# rotor.net
KiCad netlist of a schematic drawn in EAGLE
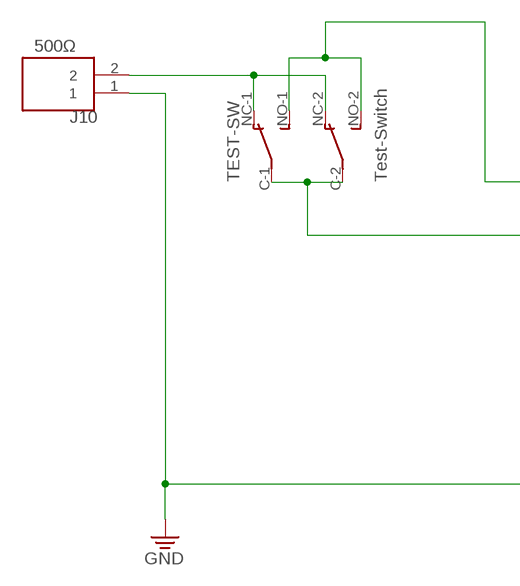
[diagram p0: schematic, sheet 1, part 1 of 2]
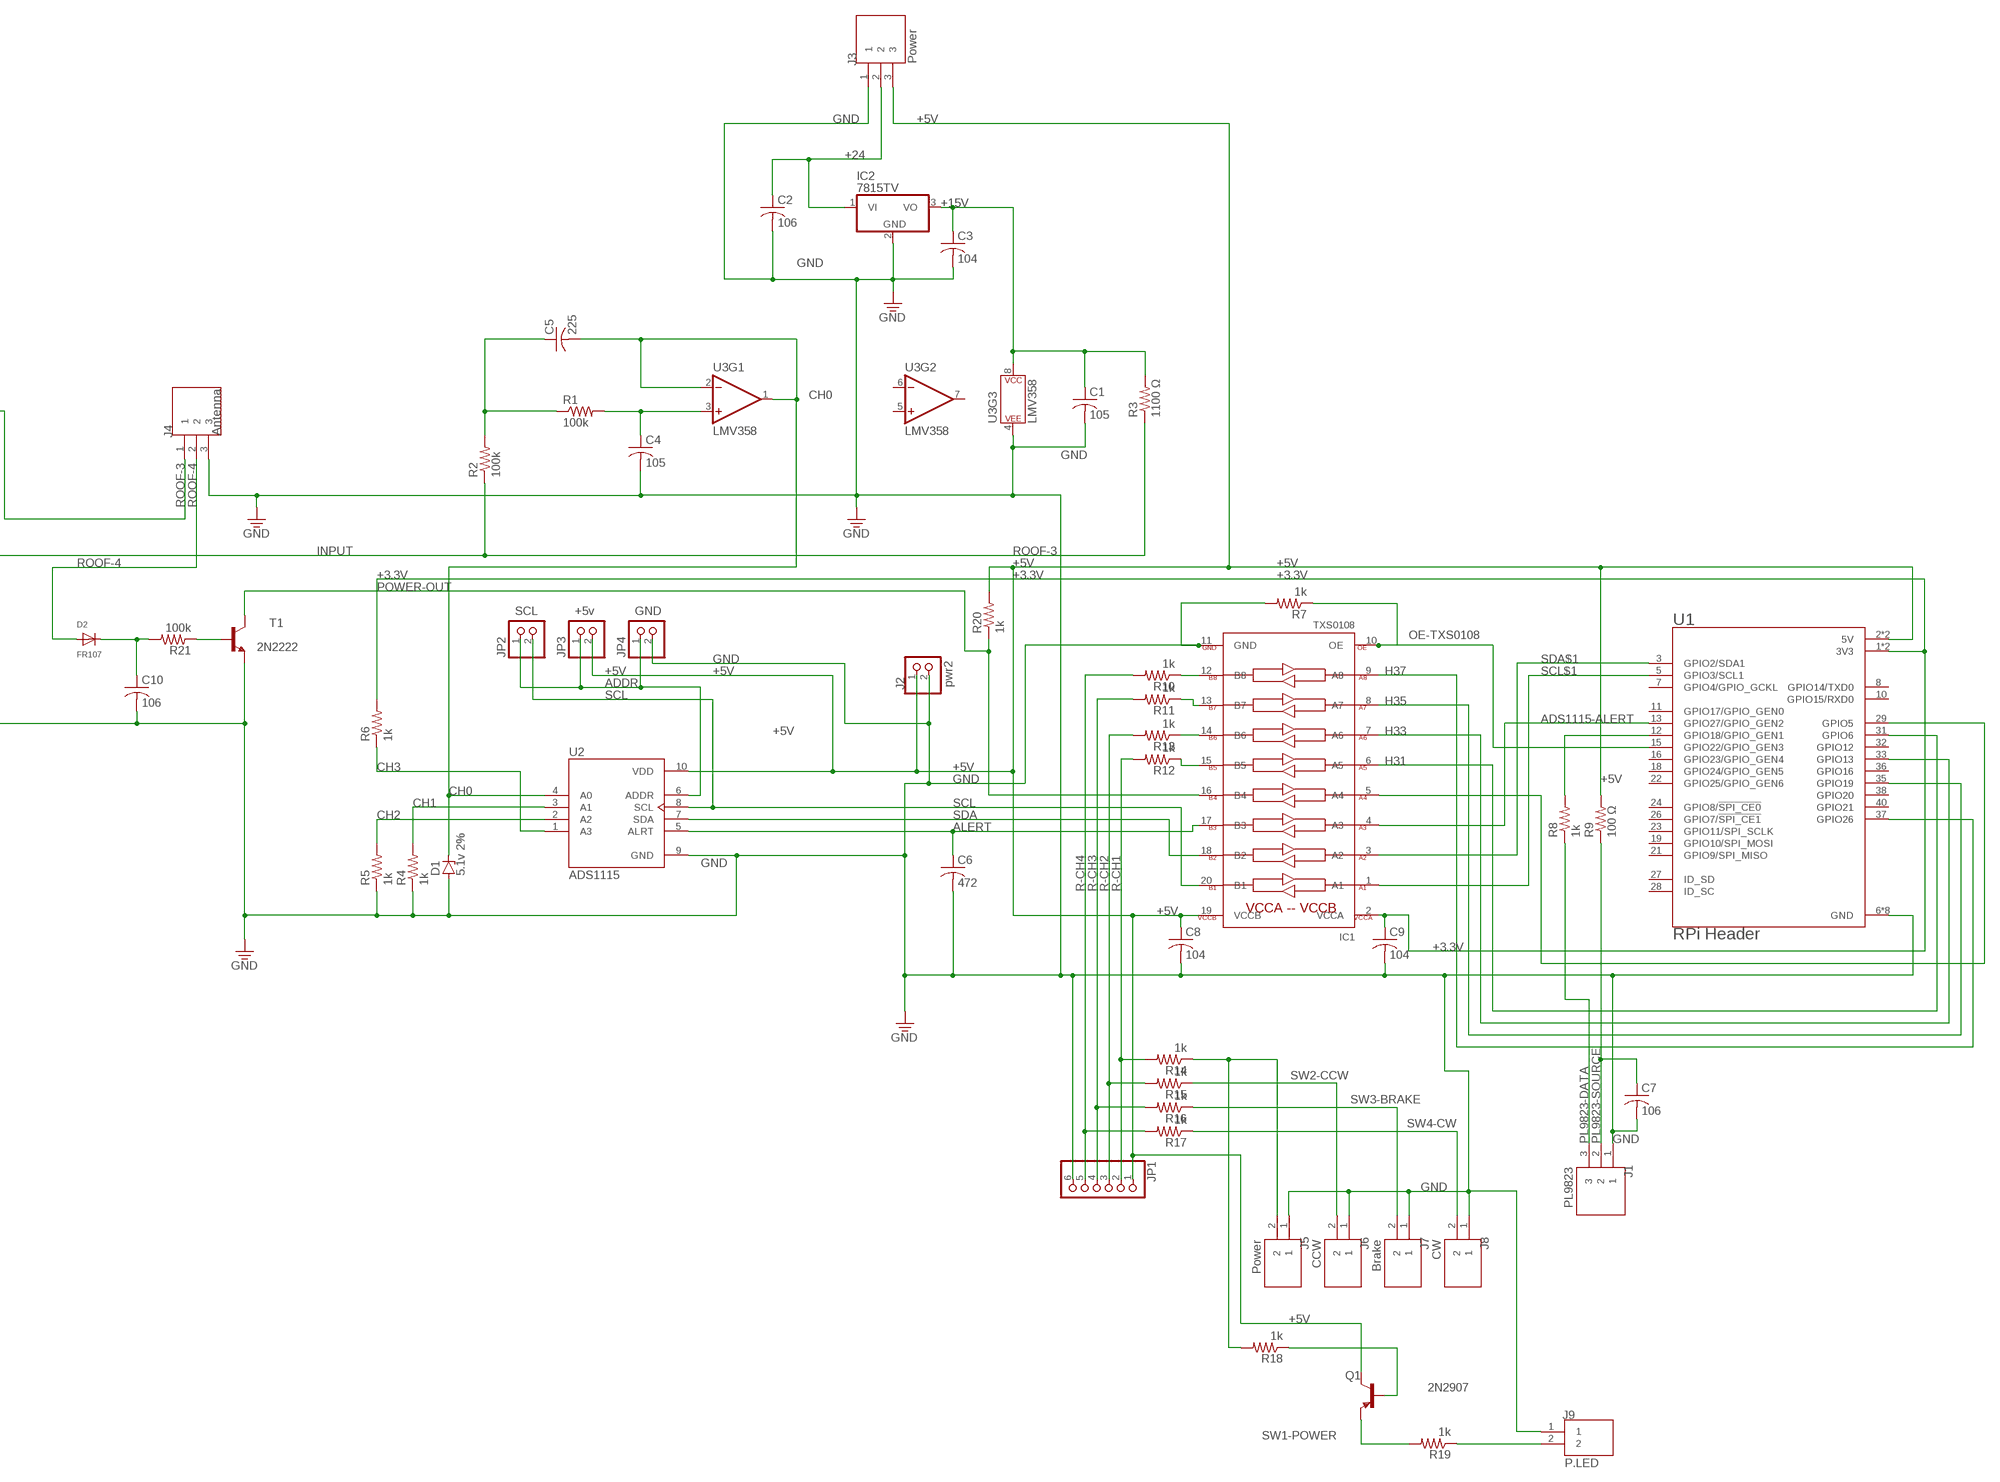
[diagram p1: schematic, sheet 1, part 2 of 2]

(export (version "E")
  (design (tool "Eeschema 10.0.6"))
  (components
    (comp (ref "C1")
      (value "105")
      (footprint "eagle-import:C0805")
      (libsource (lib "eagle-import") (part "C-USC0805"))
    )
    (comp (ref "C2")
      (value "106")
      (footprint "eagle-import:C0805")
      (libsource (lib "eagle-import") (part "C-USC0805"))
    )
    (comp (ref "C3")
      (value "104")
      (footprint "eagle-import:C0805")
      (libsource (lib "eagle-import") (part "C-USC0805"))
    )
    (comp (ref "C4")
      (value "105")
      (footprint "eagle-import:C0805")
      (libsource (lib "eagle-import") (part "C-USC0805"))
    )
    (comp (ref "C5")
      (value "225")
      (footprint "eagle-import:C0805")
      (libsource (lib "eagle-import") (part "C-USC0805"))
    )
    (comp (ref "C6")
      (value "472")
      (footprint "eagle-import:C0805")
      (libsource (lib "eagle-import") (part "C-USC0805"))
    )
    (comp (ref "C7")
      (value "106")
      (footprint "eagle-import:C0805")
      (libsource (lib "eagle-import") (part "C-USC0805"))
    )
    (comp (ref "C8")
      (value "104")
      (footprint "eagle-import:C0805")
      (libsource (lib "eagle-import") (part "C-USC0805"))
    )
    (comp (ref "C9")
      (value "104")
      (footprint "eagle-import:C0805")
      (libsource (lib "eagle-import") (part "C-USC0805"))
    )
    (comp (ref "C10")
      (value "106")
      (footprint "eagle-import:C0805")
      (libsource (lib "eagle-import") (part "C-USC0805"))
    )
    (comp (ref "D1")
      (value "5.1v 2%")
      (footprint "eagle-import:ZDIO-7.5")
      (libsource (lib "eagle-import") (part "ZENER-DIODEZD-7.5"))
    )
    (comp (ref "D2")
      (value "FR107")
      (footprint "eagle-import:SMADIODE")
      (libsource (lib "eagle-import") (part "DIODESMA"))
    )
    (comp (ref "IC1")
      (value "TXS0108")
      (footprint "eagle-import:TSSOP20")
      (fields (field (name "MF") "Texas Instruments") (field (name "MP") "TXS0108E"))
      (libsource (lib "eagle-import") (part "TXS0108EPWR"))
    )
    (comp (ref "IC2")
      (value "7815TV")
      (footprint "eagle-import:TO220V")
      (libsource (lib "eagle-import") (part "78TV15"))
    )
    (comp (ref "J1")
      (value "PL9823")
      (footprint "eagle-import:CUI_TB004-508-03BE")
      (fields (field (name "MF") "CUI Devices") (field (name "MP") "TB004 -508-03BE"))
      (libsource (lib "eagle-import") (part "TB004-508-03BE"))
    )
    (comp (ref "J2")
      (value "pwr2")
      (footprint "eagle-import:1X02")
      (libsource (lib "eagle-import") (part "pinhead_325_PINHD-1X2"))
    )
    (comp (ref "J3")
      (value "Power")
      (footprint "eagle-import:CUI_TB004-508-03BE")
      (fields (field (name "MF") "CUI Devices") (field (name "MP") "TB004 -508-03BE"))
      (libsource (lib "eagle-import") (part "TB004-508-03BE"))
    )
    (comp (ref "J4")
      (value "Antenna")
      (footprint "eagle-import:CUI_TB004-508-03BE")
      (fields (field (name "MF") "CUI Devices") (field (name "MP") "TB004 -508-03BE"))
      (libsource (lib "eagle-import") (part "TB004-508-03BE"))
    )
    (comp (ref "J5")
      (value "Power")
      (footprint "eagle-import:CUI_TB004-508-02BE")
      (fields (field (name "MF") "CUI Devices") (field (name "MP") "TB004-508-02BE"))
      (libsource (lib "eagle-import") (part "TB004-508-02BE"))
    )
    (comp (ref "J6")
      (value "CCW")
      (footprint "eagle-import:CUI_TB004-508-02BE")
      (fields (field (name "MF") "CUI Devices") (field (name "MP") "TB004-508-02BE"))
      (libsource (lib "eagle-import") (part "TB004-508-02BE"))
    )
    (comp (ref "J7")
      (value "Brake")
      (footprint "eagle-import:CUI_TB004-508-02BE")
      (fields (field (name "MF") "CUI Devices") (field (name "MP") "TB004-508-02BE"))
      (libsource (lib "eagle-import") (part "TB004-508-02BE"))
    )
    (comp (ref "J8")
      (value "CW")
      (footprint "eagle-import:CUI_TB004-508-02BE")
      (fields (field (name "MF") "CUI Devices") (field (name "MP") "TB004-508-02BE"))
      (libsource (lib "eagle-import") (part "TB004-508-02BE"))
    )
    (comp (ref "J9")
      (value "P.LED")
      (footprint "eagle-import:CUI_TB004-508-02BE")
      (fields (field (name "MF") "CUI Devices") (field (name "MP") "TB004-508-02BE"))
      (libsource (lib "eagle-import") (part "TB004-508-02BE"))
    )
    (comp (ref "J10")
      (value "500Ω ├")
      (footprint "eagle-import:CUI_TB004-508-02BE")
      (fields (field (name "MF") "CUI Devices") (field (name "MP") "TB004-508-02BE"))
      (libsource (lib "eagle-import") (part "TB004-508-02BE"))
    )
    (comp (ref "JP1")
      (value "PINHD-1X6")
      (footprint "eagle-import:1X06")
      (libsource (lib "eagle-import") (part "PINHD-1X6"))
    )
    (comp (ref "JP2")
      (value "SCL")
      (footprint "eagle-import:1X02-SPECIAL")
      (libsource (lib "eagle-import") (part "PINHD-1X2SPECIAL"))
    )
    (comp (ref "JP3")
      (value "+5v")
      (footprint "eagle-import:1X02-SPECIAL")
      (libsource (lib "eagle-import") (part "PINHD-1X2SPECIAL"))
    )
    (comp (ref "JP4")
      (value "GND")
      (footprint "eagle-import:1X02-SPECIAL")
      (libsource (lib "eagle-import") (part "PINHD-1X2SPECIAL"))
    )
    (comp (ref "Q1")
      (value "2N2907")
      (footprint "eagle-import:TO92-CBE-OVAL")
      (libsource (lib "eagle-import") (part "2N2907CBE"))
    )
    (comp (ref "R1")
      (value "100k")
      (footprint "eagle-import:M0805")
      (libsource (lib "eagle-import") (part "test_R-US_M0805"))
    )
    (comp (ref "R2")
      (value "100k")
      (footprint "eagle-import:M0805")
      (libsource (lib "eagle-import") (part "test_R-US_M0805"))
    )
    (comp (ref "R3")
      (value "1100 Ω")
      (footprint "eagle-import:M0805")
      (libsource (lib "eagle-import") (part "R-US_M0805"))
    )
    (comp (ref "R4")
      (value "1k")
      (footprint "eagle-import:M0805")
      (libsource (lib "eagle-import") (part "test_R-US_M0805"))
    )
    (comp (ref "R5")
      (value "1k")
      (footprint "eagle-import:M0805")
      (libsource (lib "eagle-import") (part "test_R-US_M0805"))
    )
    (comp (ref "R6")
      (value "1k")
      (footprint "eagle-import:M0805")
      (libsource (lib "eagle-import") (part "test_R-US_M0805"))
    )
    (comp (ref "R7")
      (value "1k")
      (footprint "eagle-import:M0805")
      (libsource (lib "eagle-import") (part "test_R-US_M0805"))
    )
    (comp (ref "R8")
      (value "1k")
      (footprint "eagle-import:M0805")
      (libsource (lib "eagle-import") (part "test_R-US_M0805"))
    )
    (comp (ref "R9")
      (value "100 Ω")
      (footprint "eagle-import:M0805")
      (libsource (lib "eagle-import") (part "test_R-US_M0805"))
    )
    (comp (ref "R10")
      (value "1k")
      (footprint "eagle-import:M0805")
      (libsource (lib "eagle-import") (part "test_R-US_M0805"))
    )
    (comp (ref "R11")
      (value "1k")
      (footprint "eagle-import:M0805")
      (libsource (lib "eagle-import") (part "test_R-US_M0805"))
    )
    (comp (ref "R12")
      (value "1k")
      (footprint "eagle-import:M0805")
      (libsource (lib "eagle-import") (part "test_R-US_M0805"))
    )
    (comp (ref "R13")
      (value "1k")
      (footprint "eagle-import:M0805")
      (libsource (lib "eagle-import") (part "test_R-US_M0805"))
    )
    (comp (ref "R14")
      (value "1k")
      (footprint "eagle-import:M0805")
      (libsource (lib "eagle-import") (part "test_R-US_M0805"))
    )
    (comp (ref "R15")
      (value "1k")
      (footprint "eagle-import:M0805")
      (libsource (lib "eagle-import") (part "test_R-US_M0805"))
    )
    (comp (ref "R16")
      (value "1k")
      (footprint "eagle-import:M0805")
      (libsource (lib "eagle-import") (part "test_R-US_M0805"))
    )
    (comp (ref "R17")
      (value "1k")
      (footprint "eagle-import:M0805")
      (libsource (lib "eagle-import") (part "test_R-US_M0805"))
    )
    (comp (ref "R18")
      (value "1k")
      (footprint "eagle-import:M0805")
      (libsource (lib "eagle-import") (part "test_R-US_M0805"))
    )
    (comp (ref "R19")
      (value "1k")
      (footprint "eagle-import:M0805")
      (libsource (lib "eagle-import") (part "test_R-US_M0805"))
    )
    (comp (ref "R20")
      (value "1k")
      (footprint "eagle-import:M0805")
      (libsource (lib "eagle-import") (part "test_R-US_M0805"))
    )
    (comp (ref "R21")
      (value "100k")
      (footprint "eagle-import:M0805")
      (libsource (lib "eagle-import") (part "test_R-US_M0805"))
    )
    (comp (ref "T1")
      (value "2N2222")
      (footprint "eagle-import:TO92-CBE-OVAL")
      (libsource (lib "eagle-import") (part "2N2222CBE"))
    )
    (comp (ref "TEST-SW")
      (value "Test-Switch")
      (footprint "eagle-import:DP-DT")
      (libsource (lib "eagle-import") (part "DPDT-SWITCH"))
    )
    (comp (ref "U1")
      (value "RPi Header")
      (footprint "eagle-import:MODULE_RASPBERRY_PI_3B+_HDR")
      (libsource (lib "eagle-import") (part "RASPBERRY_PI_3B+_HDRMODEL_RASPBEERY_PI_3B_HDR"))
    )
    (comp (ref "U2")
      (value "ADS1115")
      (footprint "eagle-import:MODULE_1115_NARROW")
      (fields (field (name "MF") "Adafruit Industries") (field (name "MP") "1085"))
      (libsource (lib "eagle-import") (part "ADS1115-BREAKOUT-NARROW"))
    )
    (comp (ref "U3")
      (value "LMV358")
      (footprint "eagle-import:SO08")
      (libsource (lib "eagle-import") (part "LM358-SOP8SOIC"))
    )
  )
  (nets
    (net (code "1") (name "/+3.3V") (class "Default")
      (node (ref "C9") (pin "1") (pinfunction "1_1") (pintype "passive"))
      (node (ref "IC1") (pin "2") (pinfunction "VCCA_2") (pintype "power_in"))
      (node (ref "R6") (pin "2") (pinfunction "2_2") (pintype "passive"))
      (node (ref "U1") (pin "1") (pinfunction "3V3_1") (pintype "power_in"))
      (node (ref "U1") (pin "17") (pinfunction "3V3_17") (pintype "power_in"))
    )
    (net (code "2") (name "/+5V") (class "Default")
      (node (ref "C8") (pin "1") (pinfunction "1_1") (pintype "passive"))
      (node (ref "IC1") (pin "19") (pinfunction "VCCB_19") (pintype "power_in"))
      (node (ref "J2") (pin "1") (pinfunction "1_1") (pintype "passive"))
      (node (ref "J3") (pin "3") (pinfunction "3_3") (pintype "passive"))
      (node (ref "JP1") (pin "1") (pinfunction "1_1") (pintype "passive"))
      (node (ref "JP3") (pin "2") (pinfunction "2_2") (pintype "passive"))
      (node (ref "Q1") (pin "C") (pinfunction "C_C") (pintype "passive"))
      (node (ref "R20") (pin "2") (pinfunction "2_2") (pintype "passive"))
      (node (ref "R9") (pin "2") (pinfunction "2_2") (pintype "passive"))
      (node (ref "U1") (pin "2") (pinfunction "5V_2") (pintype "power_in"))
      (node (ref "U1") (pin "4") (pinfunction "5V_4") (pintype "power_in"))
      (node (ref "U2") (pin "10") (pinfunction "VDD_10") (pintype "power_in"))
    )
    (net (code "3") (name "/+15V") (class "Default")
      (node (ref "C1") (pin "1") (pinfunction "1_1") (pintype "passive"))
      (node (ref "C3") (pin "1") (pinfunction "1_1") (pintype "passive"))
      (node (ref "IC2") (pin "3") (pinfunction "VO_3") (pintype "passive"))
      (node (ref "R3") (pin "2") (pinfunction "2_2") (pintype "passive"))
      (node (ref "U3") (pin "8") (pinfunction "P$V+_8") (pintype "bidirectional"))
    )
    (net (code "4") (name "/+24") (class "Default")
      (node (ref "C2") (pin "1") (pinfunction "1_1") (pintype "passive"))
      (node (ref "IC2") (pin "1") (pinfunction "VI_1") (pintype "input"))
      (node (ref "J3") (pin "2") (pinfunction "2_2") (pintype "passive"))
    )
    (net (code "5") (name "/ADDR") (class "Default")
      (node (ref "JP2") (pin "1") (pinfunction "1_1") (pintype "passive"))
      (node (ref "JP3") (pin "1") (pinfunction "1_1") (pintype "passive"))
      (node (ref "JP4") (pin "1") (pinfunction "1_1") (pintype "passive"))
      (node (ref "U2") (pin "6") (pinfunction "ADDR_6") (pintype "input"))
    )
    (net (code "6") (name "/ADS1115-ALERT") (class "Default")
      (node (ref "IC1") (pin "4") (pinfunction "A3_4") (pintype "bidirectional"))
      (node (ref "U1") (pin "13") (pinfunction "GPIO27/GPIO_GEN2_13") (pintype "bidirectional"))
    )
    (net (code "7") (name "/ALERT") (class "Default")
      (node (ref "C6") (pin "1") (pinfunction "1_1") (pintype "passive"))
      (node (ref "IC1") (pin "17") (pinfunction "B3_17") (pintype "bidirectional"))
      (node (ref "U2") (pin "5") (pinfunction "ALRT_5") (pintype "output"))
    )
    (net (code "8") (name "/CH0") (class "Default")
      (node (ref "C5") (pin "2") (pinfunction "2_2") (pintype "passive"))
      (node (ref "D1") (pin "C") (pinfunction "C_C") (pintype "passive"))
      (node (ref "U2") (pin "4") (pinfunction "A0_4") (pintype "input"))
      (node (ref "U3") (pin "1") (pinfunction "OUT_1") (pintype "output"))
      (node (ref "U3") (pin "2") (pinfunction "-IN_2") (pintype "input"))
    )
    (net (code "9") (name "/CH1") (class "Default")
      (node (ref "R4") (pin "2") (pinfunction "2_2") (pintype "passive"))
      (node (ref "U2") (pin "3") (pinfunction "A1_3") (pintype "input"))
    )
    (net (code "10") (name "/CH2") (class "Default")
      (node (ref "R5") (pin "2") (pinfunction "2_2") (pintype "passive"))
      (node (ref "U2") (pin "2") (pinfunction "A2_2") (pintype "input"))
    )
    (net (code "11") (name "/CH3") (class "Default")
      (node (ref "R6") (pin "1") (pinfunction "1_1") (pintype "passive"))
      (node (ref "U2") (pin "1") (pinfunction "A3_1") (pintype "input"))
    )
    (net (code "12") (name "/H31") (class "Default")
      (node (ref "IC1") (pin "6") (pinfunction "A5_6") (pintype "bidirectional"))
      (node (ref "U1") (pin "31") (pinfunction "GPIO6_31") (pintype "bidirectional"))
    )
    (net (code "13") (name "/H33") (class "Default")
      (node (ref "IC1") (pin "7") (pinfunction "A6_7") (pintype "bidirectional"))
      (node (ref "U1") (pin "33") (pinfunction "GPIO13_33") (pintype "bidirectional"))
    )
    (net (code "14") (name "/H35") (class "Default")
      (node (ref "IC1") (pin "8") (pinfunction "A7_8") (pintype "bidirectional"))
      (node (ref "U1") (pin "35") (pinfunction "GPIO19_35") (pintype "bidirectional"))
    )
    (net (code "15") (name "/H37") (class "Default")
      (node (ref "IC1") (pin "9") (pinfunction "A8_9") (pintype "bidirectional"))
      (node (ref "U1") (pin "37") (pinfunction "GPIO26_37") (pintype "bidirectional"))
    )
    (net (code "16") (name "/INPUT") (class "Default")
      (node (ref "R2") (pin "1") (pinfunction "1_1") (pintype "passive"))
      (node (ref "R3") (pin "1") (pinfunction "1_1") (pintype "passive"))
      (node (ref "TEST-SW") (pin "C-1") (pinfunction "C-1_C-1") (pintype "passive"))
      (node (ref "TEST-SW") (pin "C-2") (pinfunction "C-2_C-2") (pintype "passive"))
    )
    (net (code "17") (name "/OE-TXS0108") (class "Default")
      (node (ref "IC1") (pin "10") (pinfunction "OE_10") (pintype "input"))
      (node (ref "R7") (pin "1") (pinfunction "1_1") (pintype "passive"))
      (node (ref "U1") (pin "15") (pinfunction "GPIO22/GPIO_GEN3_15") (pintype "bidirectional"))
    )
    (net (code "18") (name "/PL9823-DATA") (class "Default")
      (node (ref "J1") (pin "3") (pinfunction "3_3") (pintype "passive"))
      (node (ref "R8") (pin "1") (pinfunction "1_1") (pintype "passive"))
    )
    (net (code "19") (name "/PL9823-SOURCE") (class "Default")
      (node (ref "C7") (pin "1") (pinfunction "1_1") (pintype "passive"))
      (node (ref "J1") (pin "2") (pinfunction "2_2") (pintype "passive"))
      (node (ref "R9") (pin "1") (pinfunction "1_1") (pintype "passive"))
    )
    (net (code "20") (name "/POWER-OUT") (class "Default")
      (node (ref "IC1") (pin "16") (pinfunction "B4_16") (pintype "bidirectional"))
      (node (ref "R20") (pin "1") (pinfunction "1_1") (pintype "passive"))
      (node (ref "T1") (pin "C") (pinfunction "C_C") (pintype "passive"))
    )
    (net (code "21") (name "/R-CH1") (class "Default")
      (node (ref "JP1") (pin "2") (pinfunction "2_2") (pintype "passive"))
      (node (ref "R12") (pin "2") (pinfunction "2_2") (pintype "passive"))
      (node (ref "R14") (pin "2") (pinfunction "2_2") (pintype "passive"))
    )
    (net (code "22") (name "/R-CH2") (class "Default")
      (node (ref "JP1") (pin "3") (pinfunction "3_3") (pintype "passive"))
      (node (ref "R13") (pin "2") (pinfunction "2_2") (pintype "passive"))
      (node (ref "R15") (pin "2") (pinfunction "2_2") (pintype "passive"))
    )
    (net (code "23") (name "/R-CH3") (class "Default")
      (node (ref "JP1") (pin "4") (pinfunction "4_4") (pintype "passive"))
      (node (ref "R11") (pin "2") (pinfunction "2_2") (pintype "passive"))
      (node (ref "R16") (pin "2") (pinfunction "2_2") (pintype "passive"))
    )
    (net (code "24") (name "/R-CH4") (class "Default")
      (node (ref "JP1") (pin "5") (pinfunction "5_5") (pintype "passive"))
      (node (ref "R10") (pin "2") (pinfunction "2_2") (pintype "passive"))
      (node (ref "R17") (pin "2") (pinfunction "2_2") (pintype "passive"))
    )
    (net (code "25") (name "/ROOF-3") (class "Default")
      (node (ref "J4") (pin "1") (pinfunction "1_1") (pintype "passive"))
      (node (ref "TEST-SW") (pin "NO-1") (pinfunction "NO-1_NO-1") (pintype "passive"))
      (node (ref "TEST-SW") (pin "NO-2") (pinfunction "NO-2_NO-2") (pintype "passive"))
    )
    (net (code "26") (name "/ROOF-4") (class "Default")
      (node (ref "D2") (pin "A") (pinfunction "A_A") (pintype "passive"))
      (node (ref "J4") (pin "2") (pinfunction "2_2") (pintype "passive"))
    )
    (net (code "27") (name "/SCL") (class "Default")
      (node (ref "IC1") (pin "20") (pinfunction "B1_20") (pintype "bidirectional"))
      (node (ref "JP2") (pin "2") (pinfunction "2_2") (pintype "passive"))
      (node (ref "U2") (pin "8") (pinfunction "SCL_8") (pintype "input"))
    )
    (net (code "28") (name "/SCL$1") (class "Default")
      (node (ref "IC1") (pin "1") (pinfunction "A1_1") (pintype "bidirectional"))
      (node (ref "U1") (pin "5") (pinfunction "GPIO3/SCL1_5") (pintype "bidirectional"))
    )
    (net (code "29") (name "/SDA") (class "Default")
      (node (ref "IC1") (pin "18") (pinfunction "B2_18") (pintype "bidirectional"))
      (node (ref "U2") (pin "7") (pinfunction "SDA_7") (pintype "bidirectional"))
    )
    (net (code "30") (name "/SDA$1") (class "Default")
      (node (ref "IC1") (pin "3") (pinfunction "A2_3") (pintype "bidirectional"))
      (node (ref "U1") (pin "3") (pinfunction "GPIO2/SDA1_3") (pintype "bidirectional"))
    )
    (net (code "31") (name "/SW1-POWER") (class "Default")
      (node (ref "J5") (pin "2") (pinfunction "2_2") (pintype "passive"))
      (node (ref "R14") (pin "1") (pinfunction "1_1") (pintype "passive"))
      (node (ref "R18") (pin "2") (pinfunction "2_2") (pintype "passive"))
    )
    (net (code "32") (name "/SW2-CCW") (class "Default")
      (node (ref "J6") (pin "2") (pinfunction "2_2") (pintype "passive"))
      (node (ref "R15") (pin "1") (pinfunction "1_1") (pintype "passive"))
    )
    (net (code "33") (name "/SW3-BRAKE") (class "Default")
      (node (ref "J7") (pin "2") (pinfunction "2_2") (pintype "passive"))
      (node (ref "R16") (pin "1") (pinfunction "1_1") (pintype "passive"))
    )
    (net (code "34") (name "/SW4-CW") (class "Default")
      (node (ref "J8") (pin "2") (pinfunction "2_2") (pintype "passive"))
      (node (ref "R17") (pin "1") (pinfunction "1_1") (pintype "passive"))
    )
    (net (code "35") (name "GND") (class "Default")
      (node (ref "C1") (pin "2") (pinfunction "2_2") (pintype "passive"))
      (node (ref "C10") (pin "2") (pinfunction "2_2") (pintype "passive"))
      (node (ref "C2") (pin "2") (pinfunction "2_2") (pintype "passive"))
      (node (ref "C3") (pin "2") (pinfunction "2_2") (pintype "passive"))
      (node (ref "C4") (pin "2") (pinfunction "2_2") (pintype "passive"))
      (node (ref "C6") (pin "2") (pinfunction "2_2") (pintype "passive"))
      (node (ref "C7") (pin "2") (pinfunction "2_2") (pintype "passive"))
      (node (ref "C8") (pin "2") (pinfunction "2_2") (pintype "passive"))
      (node (ref "C9") (pin "2") (pinfunction "2_2") (pintype "passive"))
      (node (ref "D1") (pin "A") (pinfunction "A_A") (pintype "passive"))
      (node (ref "IC1") (pin "11") (pinfunction "GND_11") (pintype "power_in"))
      (node (ref "IC2") (pin "2") (pinfunction "GND_2") (pintype "passive"))
      (node (ref "J1") (pin "1") (pinfunction "1_1") (pintype "passive"))
      (node (ref "J10") (pin "1") (pinfunction "1_1") (pintype "passive"))
      (node (ref "J2") (pin "2") (pinfunction "2_2") (pintype "passive"))
      (node (ref "J3") (pin "1") (pinfunction "1_1") (pintype "passive"))
      (node (ref "J4") (pin "3") (pinfunction "3_3") (pintype "passive"))
      (node (ref "J5") (pin "1") (pinfunction "1_1") (pintype "passive"))
      (node (ref "J6") (pin "1") (pinfunction "1_1") (pintype "passive"))
      (node (ref "J7") (pin "1") (pinfunction "1_1") (pintype "passive"))
      (node (ref "J8") (pin "1") (pinfunction "1_1") (pintype "passive"))
      (node (ref "J9") (pin "1") (pinfunction "1_1") (pintype "passive"))
      (node (ref "JP1") (pin "6") (pinfunction "6_6") (pintype "passive"))
      (node (ref "JP4") (pin "2") (pinfunction "2_2") (pintype "passive"))
      (node (ref "R4") (pin "1") (pinfunction "1_1") (pintype "passive"))
      (node (ref "R5") (pin "1") (pinfunction "1_1") (pintype "passive"))
      (node (ref "R7") (pin "2") (pinfunction "2_2") (pintype "passive"))
      (node (ref "T1") (pin "E") (pinfunction "E_E") (pintype "passive"))
      (node (ref "U1") (pin "14") (pinfunction "GND_14") (pintype "power_in"))
      (node (ref "U1") (pin "20") (pinfunction "GND_20") (pintype "power_in"))
      (node (ref "U1") (pin "25") (pinfunction "GND_25") (pintype "power_in"))
      (node (ref "U1") (pin "30") (pinfunction "GND_30") (pintype "power_in"))
      (node (ref "U1") (pin "34") (pinfunction "GND_34") (pintype "power_in"))
      (node (ref "U1") (pin "39") (pinfunction "GND_39") (pintype "power_in"))
      (node (ref "U1") (pin "6") (pinfunction "GND_6") (pintype "power_in"))
      (node (ref "U1") (pin "9") (pinfunction "GND_9") (pintype "power_in"))
      (node (ref "U2") (pin "9") (pinfunction "GND_9") (pintype "power_in"))
      (node (ref "U3") (pin "4") (pinfunction "P$V-_4") (pintype "bidirectional"))
    )
    (net (code "36") (name "Net-(C5-Pad1)") (class "Default")
      (node (ref "C5") (pin "1") (pinfunction "1_1") (pintype "passive"))
      (node (ref "R1") (pin "1") (pinfunction "1_1") (pintype "passive"))
      (node (ref "R2") (pin "2") (pinfunction "2_2") (pintype "passive"))
    )
    (net (code "37") (name "Net-(C10-Pad1)") (class "Default")
      (node (ref "C10") (pin "1") (pinfunction "1_1") (pintype "passive"))
      (node (ref "D2") (pin "C") (pinfunction "C_C") (pintype "passive"))
      (node (ref "R21") (pin "2") (pinfunction "2_2") (pintype "passive"))
    )
    (net (code "38") (name "Net-(IC1-A4)") (class "Default")
      (node (ref "IC1") (pin "5") (pinfunction "A4_5") (pintype "bidirectional"))
      (node (ref "U1") (pin "29") (pinfunction "GPIO5_29") (pintype "bidirectional"))
    )
    (net (code "39") (name "Net-(IC1-B5)") (class "Default")
      (node (ref "IC1") (pin "15") (pinfunction "B5_15") (pintype "bidirectional"))
      (node (ref "R12") (pin "1") (pinfunction "1_1") (pintype "passive"))
    )
    (net (code "40") (name "Net-(IC1-B6)") (class "Default")
      (node (ref "IC1") (pin "14") (pinfunction "B6_14") (pintype "bidirectional"))
      (node (ref "R13") (pin "1") (pinfunction "1_1") (pintype "passive"))
    )
    (net (code "41") (name "Net-(IC1-B7)") (class "Default")
      (node (ref "IC1") (pin "13") (pinfunction "B7_13") (pintype "bidirectional"))
      (node (ref "R11") (pin "1") (pinfunction "1_1") (pintype "passive"))
    )
    (net (code "42") (name "Net-(IC1-B8)") (class "Default")
      (node (ref "IC1") (pin "12") (pinfunction "B8_12") (pintype "bidirectional"))
      (node (ref "R10") (pin "1") (pinfunction "1_1") (pintype "passive"))
    )
    (net (code "43") (name "Net-(J9-Pad2)") (class "Default")
      (node (ref "J9") (pin "2") (pinfunction "2_2") (pintype "passive"))
      (node (ref "R19") (pin "1") (pinfunction "1_1") (pintype "passive"))
    )
    (net (code "44") (name "Net-(J10-Pad2)") (class "Default")
      (node (ref "J10") (pin "2") (pinfunction "2_2") (pintype "passive"))
      (node (ref "TEST-SW") (pin "NC-1") (pinfunction "NC-1_NC-1") (pintype "passive"))
      (node (ref "TEST-SW") (pin "NC-2") (pinfunction "NC-2_NC-2") (pintype "passive"))
    )
    (net (code "45") (name "Net-(Q1-PadB)") (class "Default")
      (node (ref "Q1") (pin "B") (pinfunction "B_B") (pintype "passive"))
      (node (ref "R18") (pin "1") (pinfunction "1_1") (pintype "passive"))
    )
    (net (code "46") (name "Net-(Q1-PadE)") (class "Default")
      (node (ref "Q1") (pin "E") (pinfunction "E_E") (pintype "passive"))
      (node (ref "R19") (pin "2") (pinfunction "2_2") (pintype "passive"))
    )
    (net (code "47") (name "Net-(R21-Pad1)") (class "Default")
      (node (ref "R21") (pin "1") (pinfunction "1_1") (pintype "passive"))
      (node (ref "T1") (pin "B") (pinfunction "B_B") (pintype "passive"))
    )
    (net (code "48") (name "Net-(U1-GPIO18{slash}GPIO_GEN1)") (class "Default")
      (node (ref "R8") (pin "2") (pinfunction "2_2") (pintype "passive"))
      (node (ref "U1") (pin "12") (pinfunction "GPIO18/GPIO_GEN1_12") (pintype "bidirectional"))
    )
    (net (code "49") (name "Net-(U3A-+IN)") (class "Default")
      (node (ref "C4") (pin "1") (pinfunction "1_1") (pintype "passive"))
      (node (ref "R1") (pin "2") (pinfunction "2_2") (pintype "passive"))
      (node (ref "U3") (pin "3") (pinfunction "+IN_3") (pintype "input"))
    )
    (net (code "50") (name "unconnected-(U1-GPIO4{slash}GPIO_GCKL-Pad7)") (class "Default")
      (node (ref "U1") (pin "7") (pinfunction "GPIO4/GPIO_GCKL_7") (pintype "bidirectional"))
    )
    (net (code "51") (name "unconnected-(U1-GPIO7{slash}~{SPI_CE1}-Pad26)") (class "Default")
      (node (ref "U1") (pin "26") (pinfunction "GPIO7/~{SPI_CE1}_26") (pintype "bidirectional"))
    )
    (net (code "52") (name "unconnected-(U1-GPIO8{slash}~{SPI_CE0}-Pad24)") (class "Default")
      (node (ref "U1") (pin "24") (pinfunction "GPIO8/~{SPI_CE0}_24") (pintype "bidirectional"))
    )
    (net (code "53") (name "unconnected-(U1-GPIO9{slash}SPI_MISO-Pad21)") (class "Default")
      (node (ref "U1") (pin "21") (pinfunction "GPIO9/SPI_MISO_21") (pintype "bidirectional"))
    )
    (net (code "54") (name "unconnected-(U1-GPIO10{slash}SPI_MOSI-Pad19)") (class "Default")
      (node (ref "U1") (pin "19") (pinfunction "GPIO10/SPI_MOSI_19") (pintype "bidirectional"))
    )
    (net (code "55") (name "unconnected-(U1-GPIO11{slash}SPI_SCLK-Pad23)") (class "Default")
      (node (ref "U1") (pin "23") (pinfunction "GPIO11/SPI_SCLK_23") (pintype "bidirectional"))
    )
    (net (code "56") (name "unconnected-(U1-GPIO12-Pad32)") (class "Default")
      (node (ref "U1") (pin "32") (pinfunction "GPIO12_32") (pintype "bidirectional"))
    )
    (net (code "57") (name "unconnected-(U1-GPIO14{slash}TXD0-Pad8)") (class "Default")
      (node (ref "U1") (pin "8") (pinfunction "GPIO14/TXD0_8") (pintype "bidirectional"))
    )
    (net (code "58") (name "unconnected-(U1-GPIO15{slash}RXD0-Pad10)") (class "Default")
      (node (ref "U1") (pin "10") (pinfunction "GPIO15/RXD0_10") (pintype "bidirectional"))
    )
    (net (code "59") (name "unconnected-(U1-GPIO16-Pad36)") (class "Default")
      (node (ref "U1") (pin "36") (pinfunction "GPIO16_36") (pintype "bidirectional"))
    )
    (net (code "60") (name "unconnected-(U1-GPIO17{slash}GPIO_GEN0-Pad11)") (class "Default")
      (node (ref "U1") (pin "11") (pinfunction "GPIO17/GPIO_GEN0_11") (pintype "bidirectional"))
    )
    (net (code "61") (name "unconnected-(U1-GPIO20-Pad38)") (class "Default")
      (node (ref "U1") (pin "38") (pinfunction "GPIO20_38") (pintype "bidirectional"))
    )
    (net (code "62") (name "unconnected-(U1-GPIO21-Pad40)") (class "Default")
      (node (ref "U1") (pin "40") (pinfunction "GPIO21_40") (pintype "bidirectional"))
    )
    (net (code "63") (name "unconnected-(U1-GPIO23{slash}GPIO_GEN4-Pad16)") (class "Default")
      (node (ref "U1") (pin "16") (pinfunction "GPIO23/GPIO_GEN4_16") (pintype "bidirectional"))
    )
    (net (code "64") (name "unconnected-(U1-GPIO24{slash}GPIO_GEN5-Pad18)") (class "Default")
      (node (ref "U1") (pin "18") (pinfunction "GPIO24/GPIO_GEN5_18") (pintype "bidirectional"))
    )
    (net (code "65") (name "unconnected-(U1-GPIO25{slash}GPIO_GEN6-Pad22)") (class "Default")
      (node (ref "U1") (pin "22") (pinfunction "GPIO25/GPIO_GEN6_22") (pintype "bidirectional"))
    )
    (net (code "66") (name "unconnected-(U1-ID_SC-Pad28)") (class "Default")
      (node (ref "U1") (pin "28") (pinfunction "ID_SC_28") (pintype "bidirectional"))
    )
    (net (code "67") (name "unconnected-(U1-ID_SD-Pad27)") (class "Default")
      (node (ref "U1") (pin "27") (pinfunction "ID_SD_27") (pintype "bidirectional"))
    )
    (net (code "68") (name "unconnected-(U3B-+IN-Pad5)") (class "Default")
      (node (ref "U3") (pin "5") (pinfunction "+IN_5") (pintype "input"))
    )
    (net (code "69") (name "unconnected-(U3B--IN-Pad6)") (class "Default")
      (node (ref "U3") (pin "6") (pinfunction "-IN_6") (pintype "input"))
    )
    (net (code "70") (name "unconnected-(U3B-OUT-Pad7)") (class "Default")
      (node (ref "U3") (pin "7") (pinfunction "OUT_7") (pintype "output"))
    )
  )
)
